# Sheet2.net
KiCad netlist of a schematic drawn in Altium Designer
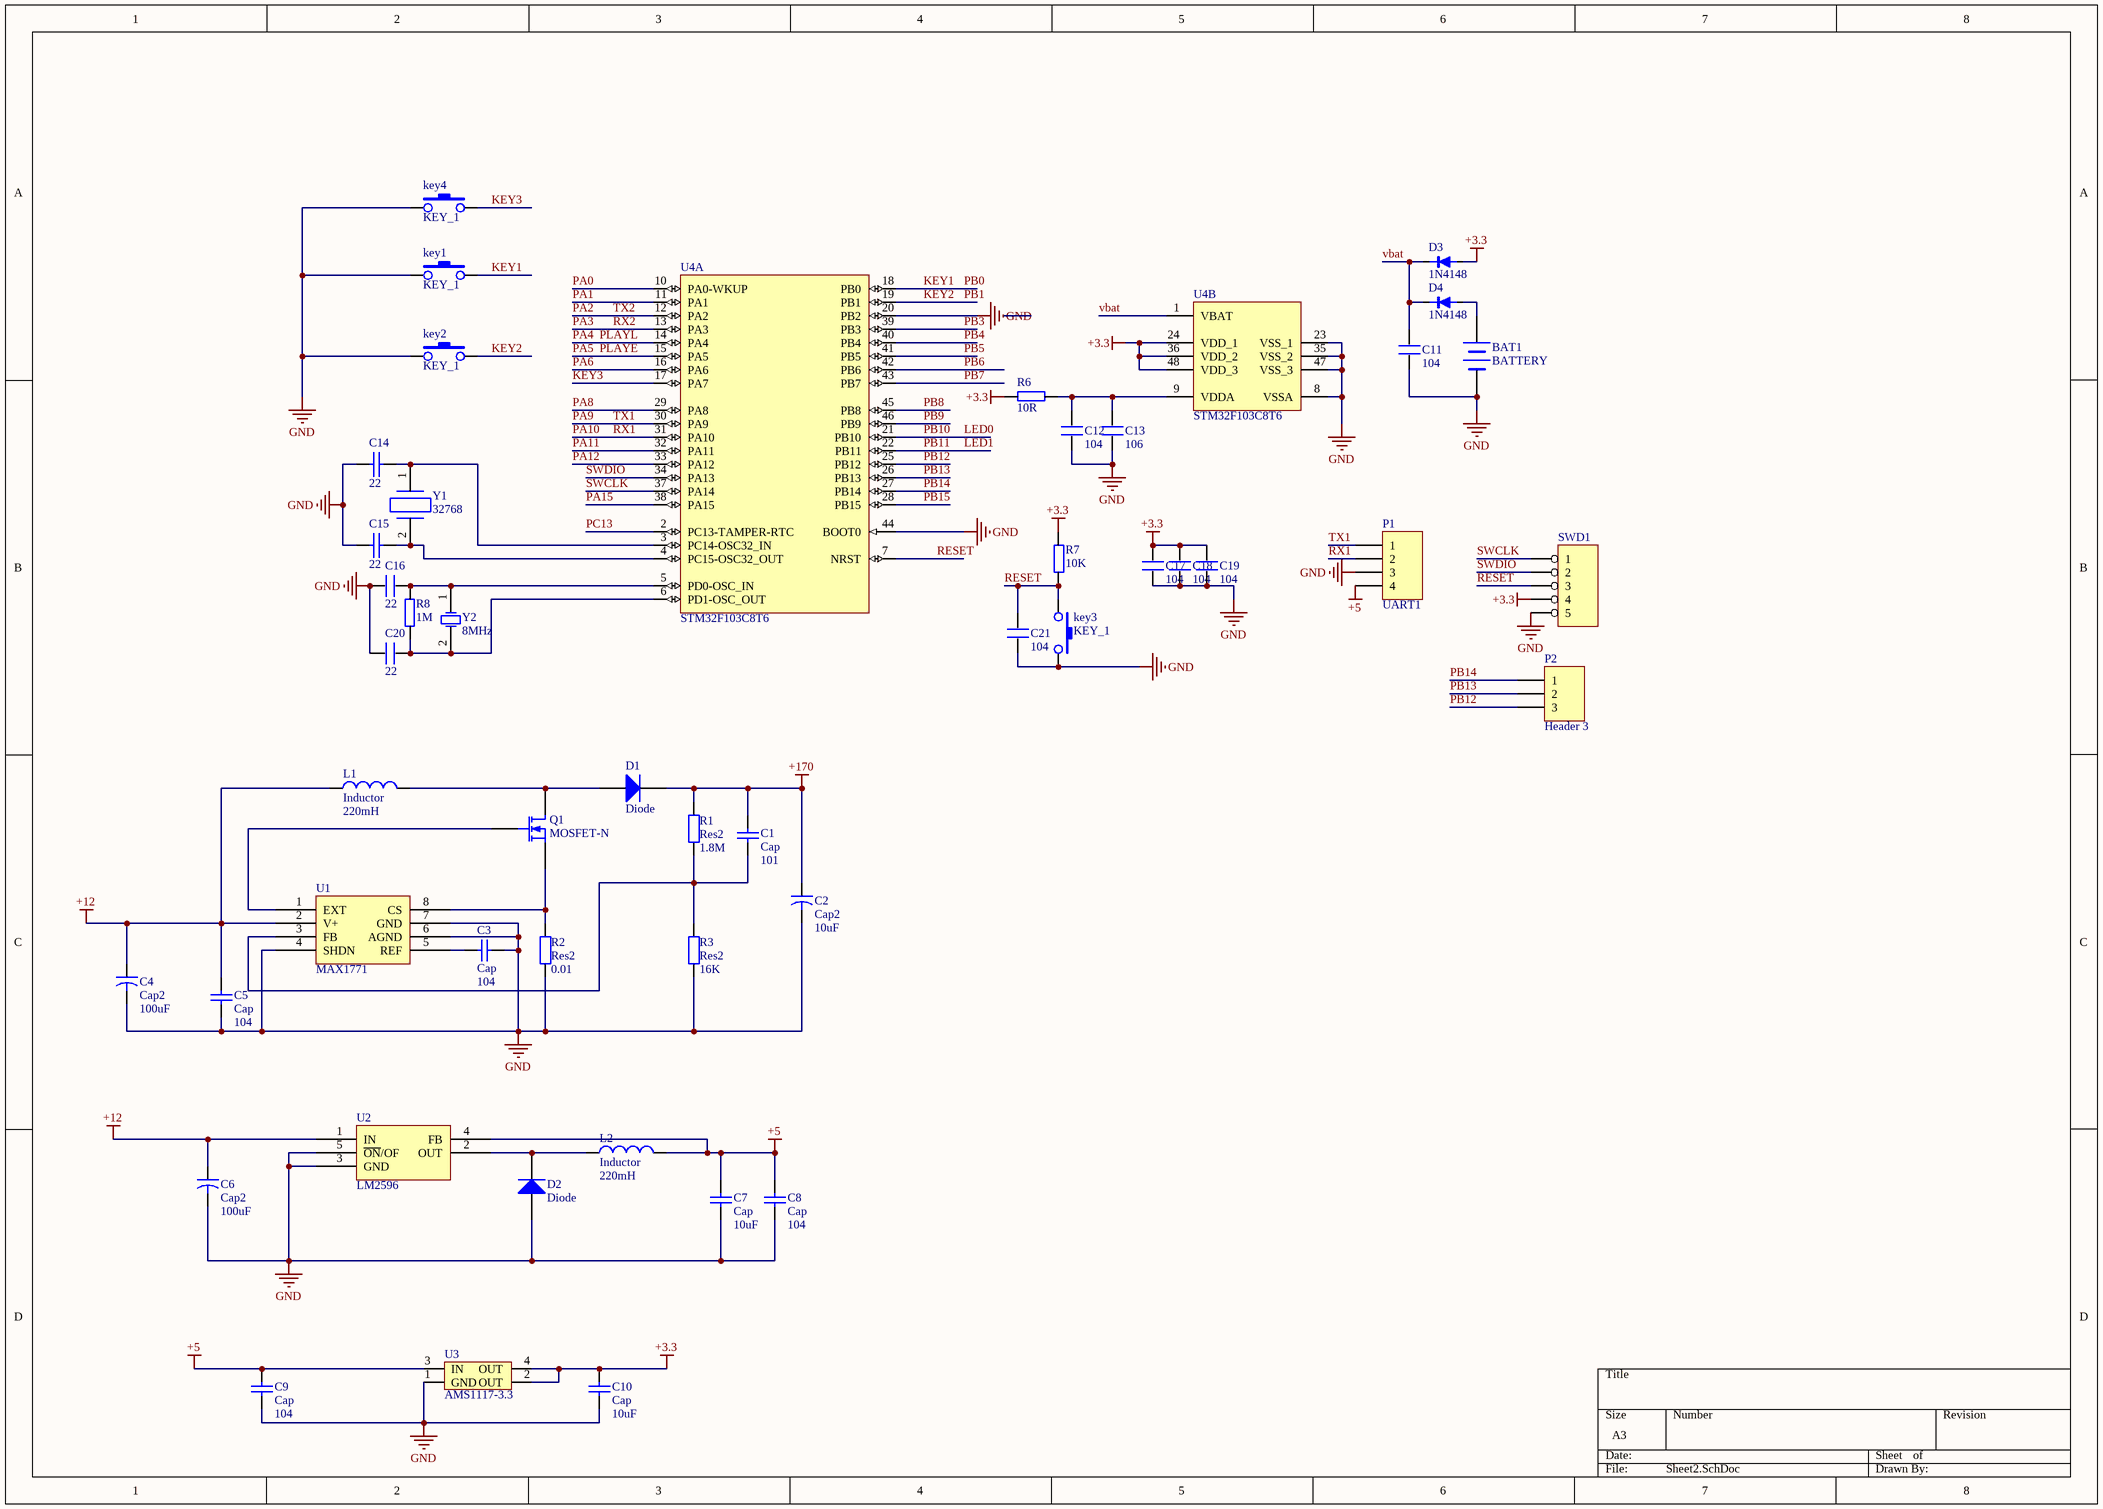
[diagram p0: Sheet2.SchDoc]

(export (version "E")
  (design (tool "Eeschema 10.0.6"))
  (components
    (comp (ref "BAT1") (value "BATTERY") (footprint "CR1220") (libsource (lib "常用元件库") (part "BATTERY")))
    (comp (ref "C1")
      (value "Cap")
      (footprint "1206C")
      (description "Capacitor")
      (fields (field (name "ALTIUM_VALUE") "101") (field (name "PUBLISHER") "Altium Limited"))
      (libsource (lib "Miscellaneous Devices") (part "Cap"))
    )
    (comp (ref "C2")
      (value "Cap2")
      (footprint "C10x16")
      (description "Capacitor")
      (fields (field (name "ALTIUM_VALUE") "10uF") (field (name "PUBLISHER") "Altium Limited"))
      (libsource (lib "Miscellaneous Devices") (part "Cap2"))
    )
    (comp (ref "C3")
      (value "Cap")
      (footprint "0805-0c")
      (description "Capacitor")
      (fields (field (name "ALTIUM_VALUE") "104") (field (name "PUBLISHER") "Altium Limited"))
      (libsource (lib "Miscellaneous Devices") (part "Cap"))
    )
    (comp (ref "C4")
      (value "Cap2")
      (footprint "C5X8")
      (description "Capacitor")
      (fields (field (name "ALTIUM_VALUE") "100uF") (field (name "PUBLISHER") "Altium Limited"))
      (libsource (lib "Miscellaneous Devices") (part "Cap2"))
    )
    (comp (ref "C5")
      (value "Cap")
      (footprint "0805-0c")
      (description "Capacitor")
      (fields (field (name "ALTIUM_VALUE") "104") (field (name "PUBLISHER") "Altium Limited"))
      (libsource (lib "Miscellaneous Devices") (part "Cap"))
    )
    (comp (ref "C6")
      (value "Cap2")
      (footprint "C5X8")
      (description "Capacitor")
      (fields (field (name "ALTIUM_VALUE") "100uF") (field (name "PUBLISHER") "Altium Limited"))
      (libsource (lib "Miscellaneous Devices") (part "Cap2"))
    )
    (comp (ref "C7")
      (value "Cap")
      (footprint "0805-0c")
      (description "Capacitor")
      (fields (field (name "ALTIUM_VALUE") "10uF") (field (name "PUBLISHER") "Altium Limited"))
      (libsource (lib "Miscellaneous Devices") (part "Cap"))
    )
    (comp (ref "C8")
      (value "Cap")
      (footprint "0805-0c")
      (description "Capacitor")
      (fields (field (name "ALTIUM_VALUE") "104") (field (name "PUBLISHER") "Altium Limited"))
      (libsource (lib "Miscellaneous Devices") (part "Cap"))
    )
    (comp (ref "C9")
      (value "Cap")
      (footprint "0805-0c")
      (description "Capacitor")
      (fields (field (name "ALTIUM_VALUE") "104") (field (name "PUBLISHER") "Altium Limited"))
      (libsource (lib "Miscellaneous Devices") (part "Cap"))
    )
    (comp (ref "C10")
      (value "Cap")
      (footprint "0805-0c")
      (description "Capacitor")
      (fields (field (name "ALTIUM_VALUE") "10uF") (field (name "PUBLISHER") "Altium Limited"))
      (libsource (lib "Miscellaneous Devices") (part "Cap"))
    )
    (comp (ref "C11") (value "104") (footprint "0805-0c") (libsource (lib "EXPLORER") (part "C")))
    (comp (ref "C12") (value "104") (footprint "0805-0c") (libsource (lib "EXPLORER") (part "C")))
    (comp (ref "C13") (value "106") (footprint "0805-0c") (libsource (lib "EXPLORER") (part "C")))
    (comp (ref "C14")
      (value "22")
      (footprint "0805-0c")
      (description "Capacitor")
      (libsource (lib "电容") (part "普通电容"))
    )
    (comp (ref "C15")
      (value "22")
      (footprint "0805-0c")
      (description "Capacitor")
      (libsource (lib "电容") (part "普通电容"))
    )
    (comp (ref "C16") (value "22") (footprint "0805-0c") (libsource (lib "EXPLORER") (part "C")))
    (comp (ref "C17") (value "104") (footprint "0805-0c") (libsource (lib "战舰STM32开发板底板封装库") (part "C")))
    (comp (ref "C18") (value "104") (footprint "0805-0c") (libsource (lib "战舰STM32开发板底板封装库") (part "C")))
    (comp (ref "C19") (value "104") (footprint "0805-0c") (libsource (lib "战舰STM32开发板底板封装库") (part "C")))
    (comp (ref "C20") (value "22") (footprint "0805-0c") (libsource (lib "EXPLORER") (part "C")))
    (comp (ref "C21") (value "104") (footprint "0805-0c") (libsource (lib "EXPLORER") (part "C")))
    (comp (ref "D1")
      (value "Diode")
      (footprint "DO-214")
      (description "Default Diode")
      (fields (field (name "PUBLISHER") "Altium Limited"))
      (libsource (lib "Miscellaneous Devices") (part "Diode"))
    )
    (comp (ref "D2")
      (value "Diode")
      (footprint "DO-214")
      (description "Default Diode")
      (fields (field (name "PUBLISHER") "Altium Limited"))
      (libsource (lib "Miscellaneous Devices") (part "Diode"))
    )
    (comp (ref "D3") (value "1N4148") (footprint "DO-214") (libsource (lib "元件库") (part "DIODE1")))
    (comp (ref "D4") (value "1N4148") (footprint "DO-214") (libsource (lib "元件库") (part "DIODE1")))
    (comp (ref "key1") (value "KEY_1") (footprint "KEY-DIP4W") (libsource (lib "元件库") (part "KEY_1")))
    (comp (ref "key2") (value "KEY_1") (footprint "KEY-DIP4W") (libsource (lib "元件库") (part "KEY_1")))
    (comp (ref "key3") (value "KEY_1") (footprint "KEY-SMD1") (libsource (lib "元件库") (part "KEY_1")))
    (comp (ref "key4") (value "KEY_1") (footprint "KEY-DIP4W") (libsource (lib "元件库") (part "KEY_1")))
    (comp (ref "L1")
      (value "Inductor")
      (footprint "L7X7")
      (fields (field (name "ALTIUM_VALUE") "220mH") (field (name "PUBLISHER") "Altium Limited"))
      (libsource (lib "Miscellaneous Devices") (part "Inductor"))
    )
    (comp (ref "L2")
      (value "Inductor")
      (footprint "L7X7")
      (fields (field (name "ALTIUM_VALUE") "220mH") (field (name "PUBLISHER") "Altium Limited"))
      (libsource (lib "Miscellaneous Devices") (part "Inductor"))
    )
    (comp (ref "P1")
      (value "UART1")
      (footprint "HDR1X4")
      (description "Header, 4-Pin")
      (fields (field (name "PUBLISHER") "Altium Limited"))
      (libsource (lib "EXPLORER") (part "Header 4"))
    )
    (comp (ref "P2")
      (value "Header 3")
      (footprint "HDR1X3")
      (description "Header, 3-Pin")
      (fields (field (name "PUBLISHER") "Altium Limited"))
      (libsource (lib "Miscellaneous Connectors") (part "Header 3"))
    )
    (comp (ref "Q1")
      (value "MOSFET-N")
      (footprint "TO-263-3")
      (description "N-Channel MOSFET")
      (fields (field (name "PUBLISHER") "Altium Limited"))
      (libsource (lib "Miscellaneous Devices") (part "MOSFET-N"))
    )
    (comp (ref "R1")
      (value "Res2")
      (footprint "0805-0r")
      (description "Resistor")
      (fields (field (name "ALTIUM_VALUE") "1.8M") (field (name "PUBLISHER") "Altium Limited"))
      (libsource (lib "Miscellaneous Devices") (part "Res2"))
    )
    (comp (ref "R2")
      (value "Res2")
      (footprint "0805-0r")
      (description "Resistor")
      (fields (field (name "ALTIUM_VALUE") "0.01") (field (name "PUBLISHER") "Altium Limited"))
      (libsource (lib "Miscellaneous Devices") (part "Res2"))
    )
    (comp (ref "R3")
      (value "Res2")
      (footprint "0805-0r")
      (description "Resistor")
      (fields (field (name "ALTIUM_VALUE") "16K") (field (name "PUBLISHER") "Altium Limited"))
      (libsource (lib "Miscellaneous Devices") (part "Res2"))
    )
    (comp (ref "R6") (value "10R") (footprint "0805-0r") (libsource (lib "EXPLORER") (part "R")))
    (comp (ref "R7") (value "10K") (footprint "0805-0r") (libsource (lib "EXPLORER") (part "R")))
    (comp (ref "R8") (value "1M") (footprint "0805-0r") (libsource (lib "EXPLORER") (part "R")))
    (comp (ref "SWD1") (value "HEADER 5") (footprint "HDR1X5") (libsource (lib "杂元件库") (part "HEADER 5")))
    (comp (ref "U1") (value "MAX1771") (footprint "sop8") (libsource (lib "Schlib1") (part "Component_1")))
    (comp (ref "U2")
      (value "LM2596")
      (footprint "TO263-5")
      (libsource (lib "LM2596-5V") (part "Component_1"))
    )
    (comp (ref "U3")
      (value "AMS1117-3.3")
      (footprint "SOT-223")
      (libsource (lib "战舰STM32开发板底板封装库") (part "AMS1117"))
    )
    (comp (ref "U4")
      (value "STM32F103C8T6")
      (footprint "STM-LQFP48_N")
      (libsource (lib "STMicroelectronics STM32 F1") (part "STM32F103C8T6"))
    )
    (comp (ref "Y1") (value "32768") (footprint "XTAL3X8") (libsource (lib "元件库") (part "XTAL")))
    (comp (ref "Y2")
      (value "8MHz")
      (footprint "XTAL-49S-DIP")
      (description "Crystal Oscillator")
      (fields (field (name "PUBLISHER") "Altium Limited"))
      (libsource (lib "EXPLORER") (part "XTAL"))
    )
  )
  (nets
    (net (code "1") (name "+3.3") (class "Default")
      (node (ref "C10") (pin "2") (pinfunction "2_2") (pintype "passive"))
      (node (ref "C17") (pin "2") (pintype "passive"))
      (node (ref "C18") (pin "2") (pintype "passive"))
      (node (ref "C19") (pin "2") (pintype "passive"))
      (node (ref "D3") (pin "1") (pinfunction "A_1") (pintype "passive"))
      (node (ref "R6") (pin "2") (pintype "passive"))
      (node (ref "R7") (pin "2") (pintype "passive"))
      (node (ref "SWD1") (pin "4") (pinfunction "4_4") (pintype "passive"))
      (node (ref "U3") (pin "2") (pinfunction "OUT_2") (pintype "passive"))
      (node (ref "U3") (pin "4") (pinfunction "OUT_4") (pintype "passive"))
      (node (ref "U4") (pin "24") (pinfunction "VDD_1_24") (pintype "power_in"))
      (node (ref "U4") (pin "36") (pinfunction "VDD_2_36") (pintype "power_in"))
      (node (ref "U4") (pin "48") (pinfunction "VDD_3_48") (pintype "power_in"))
    )
    (net (code "2") (name "+5") (class "Default")
      (node (ref "C7") (pin "2") (pinfunction "2_2") (pintype "passive"))
      (node (ref "C8") (pin "2") (pinfunction "2_2") (pintype "passive"))
      (node (ref "C9") (pin "2") (pinfunction "2_2") (pintype "passive"))
      (node (ref "L2") (pin "2") (pinfunction "2_2") (pintype "passive"))
      (node (ref "P1") (pin "4") (pinfunction "4_4") (pintype "passive"))
      (node (ref "U2") (pin "4") (pinfunction "FB_4") (pintype "passive"))
      (node (ref "U3") (pin "3") (pinfunction "IN_3") (pintype "passive"))
    )
    (net (code "3") (name "+12") (class "Default")
      (node (ref "C4") (pin "1") (pinfunction "1_1") (pintype "passive"))
      (node (ref "C5") (pin "2") (pinfunction "2_2") (pintype "passive"))
      (node (ref "C6") (pin "1") (pinfunction "1_1") (pintype "passive"))
      (node (ref "L1") (pin "1") (pinfunction "1_1") (pintype "passive"))
      (node (ref "U1") (pin "2") (pinfunction "V+_2") (pintype "passive"))
      (node (ref "U2") (pin "1") (pinfunction "IN_1") (pintype "passive"))
    )
    (net (code "4") (name "+170") (class "Default")
      (node (ref "C1") (pin "2") (pinfunction "2_2") (pintype "passive"))
      (node (ref "C2") (pin "1") (pinfunction "1_1") (pintype "passive"))
      (node (ref "D1") (pin "2") (pinfunction "K_2") (pintype "passive"))
      (node (ref "R1") (pin "2") (pinfunction "2_2") (pintype "passive"))
    )
    (net (code "5") (name "/KEY1") (class "Default")
      (node (ref "U4") (pin "18") (pinfunction "PB0_18") (pintype "bidirectional"))
      (node (ref "key1") (pin "2") (pinfunction "2_2") (pintype "passive"))
    )
    (net (code "6") (name "/KEY2") (class "Default")
      (node (ref "U4") (pin "19") (pinfunction "PB1_19") (pintype "bidirectional"))
      (node (ref "key2") (pin "2") (pinfunction "2_2") (pintype "passive"))
    )
    (net (code "7") (name "/KEY3") (class "Default")
      (node (ref "U4") (pin "17") (pinfunction "PA7_17") (pintype "bidirectional"))
      (node (ref "key4") (pin "2") (pinfunction "2_2") (pintype "passive"))
    )
    (net (code "8") (name "/LED0") (class "Default")
      (node (ref "U4") (pin "21") (pinfunction "PB10_21") (pintype "bidirectional"))
    )
    (net (code "9") (name "/LED1") (class "Default")
      (node (ref "U4") (pin "22") (pinfunction "PB11_22") (pintype "bidirectional"))
    )
    (net (code "10") (name "/PA0") (class "Default")
      (node (ref "U4") (pin "10") (pinfunction "PA0-WKUP_10") (pintype "bidirectional"))
    )
    (net (code "11") (name "/PA1") (class "Default")
      (node (ref "U4") (pin "11") (pinfunction "PA1_11") (pintype "bidirectional"))
    )
    (net (code "12") (name "/PA2") (class "Default")
      (node (ref "U4") (pin "12") (pinfunction "PA2_12") (pintype "bidirectional"))
    )
    (net (code "13") (name "/PA3") (class "Default")
      (node (ref "U4") (pin "13") (pinfunction "PA3_13") (pintype "bidirectional"))
    )
    (net (code "14") (name "/PA4") (class "Default")
      (node (ref "U4") (pin "14") (pinfunction "PA4_14") (pintype "bidirectional"))
    )
    (net (code "15") (name "/PA5") (class "Default")
      (node (ref "U4") (pin "15") (pinfunction "PA5_15") (pintype "bidirectional"))
    )
    (net (code "16") (name "/PA6") (class "Default")
      (node (ref "U4") (pin "16") (pinfunction "PA6_16") (pintype "bidirectional"))
    )
    (net (code "17") (name "/PA8") (class "Default")
      (node (ref "U4") (pin "29") (pinfunction "PA8_29") (pintype "bidirectional"))
    )
    (net (code "18") (name "/PA9") (class "Default")
      (node (ref "P1") (pin "1") (pinfunction "1_1") (pintype "passive"))
      (node (ref "U4") (pin "30") (pinfunction "PA9_30") (pintype "bidirectional"))
    )
    (net (code "19") (name "/PA10") (class "Default")
      (node (ref "P1") (pin "2") (pinfunction "2_2") (pintype "passive"))
      (node (ref "U4") (pin "31") (pinfunction "PA10_31") (pintype "bidirectional"))
    )
    (net (code "20") (name "/PA11") (class "Default")
      (node (ref "U4") (pin "32") (pinfunction "PA11_32") (pintype "bidirectional"))
    )
    (net (code "21") (name "/PA12") (class "Default")
      (node (ref "U4") (pin "33") (pinfunction "PA12_33") (pintype "bidirectional"))
    )
    (net (code "22") (name "/PA15") (class "Default")
      (node (ref "U4") (pin "38") (pinfunction "PA15_38") (pintype "bidirectional"))
    )
    (net (code "23") (name "/PB3") (class "Default")
      (node (ref "U4") (pin "39") (pinfunction "PB3_39") (pintype "bidirectional"))
    )
    (net (code "24") (name "/PB4") (class "Default")
      (node (ref "U4") (pin "40") (pinfunction "PB4_40") (pintype "bidirectional"))
    )
    (net (code "25") (name "/PB5") (class "Default")
      (node (ref "U4") (pin "41") (pinfunction "PB5_41") (pintype "bidirectional"))
    )
    (net (code "26") (name "/PB6") (class "Default")
      (node (ref "U4") (pin "42") (pinfunction "PB6_42") (pintype "bidirectional"))
    )
    (net (code "27") (name "/PB7") (class "Default")
      (node (ref "U4") (pin "43") (pinfunction "PB7_43") (pintype "bidirectional"))
    )
    (net (code "28") (name "/PB8") (class "Default")
      (node (ref "U4") (pin "45") (pinfunction "PB8_45") (pintype "bidirectional"))
    )
    (net (code "29") (name "/PB9") (class "Default")
      (node (ref "U4") (pin "46") (pinfunction "PB9_46") (pintype "bidirectional"))
    )
    (net (code "30") (name "/PB12") (class "Default")
      (node (ref "P2") (pin "3") (pinfunction "3_3") (pintype "passive"))
      (node (ref "U4") (pin "25") (pinfunction "PB12_25") (pintype "bidirectional"))
    )
    (net (code "31") (name "/PB13") (class "Default")
      (node (ref "P2") (pin "2") (pinfunction "2_2") (pintype "passive"))
      (node (ref "U4") (pin "26") (pinfunction "PB13_26") (pintype "bidirectional"))
    )
    (net (code "32") (name "/PB14") (class "Default")
      (node (ref "P2") (pin "1") (pinfunction "1_1") (pintype "passive"))
      (node (ref "U4") (pin "27") (pinfunction "PB14_27") (pintype "bidirectional"))
    )
    (net (code "33") (name "/PB15") (class "Default")
      (node (ref "U4") (pin "28") (pinfunction "PB15_28") (pintype "bidirectional"))
    )
    (net (code "34") (name "/PC13") (class "Default")
      (node (ref "U4") (pin "2") (pinfunction "PC13-TAMPER-RTC_2") (pintype "bidirectional"))
    )
    (net (code "35") (name "/RESET") (class "Default")
      (node (ref "C21") (pin "1") (pintype "passive"))
      (node (ref "R7") (pin "1") (pintype "passive"))
      (node (ref "SWD1") (pin "3") (pinfunction "3_3") (pintype "passive"))
      (node (ref "U4") (pin "7") (pinfunction "NRST_7") (pintype "bidirectional"))
      (node (ref "key3") (pin "1") (pinfunction "1_1") (pintype "passive"))
    )
    (net (code "36") (name "/SWCLK") (class "Default")
      (node (ref "SWD1") (pin "1") (pinfunction "1_1") (pintype "passive"))
      (node (ref "U4") (pin "37") (pinfunction "PA14_37") (pintype "bidirectional"))
    )
    (net (code "37") (name "/SWDIO") (class "Default")
      (node (ref "SWD1") (pin "2") (pinfunction "2_2") (pintype "passive"))
      (node (ref "U4") (pin "34") (pinfunction "PA13_34") (pintype "bidirectional"))
    )
    (net (code "38") (name "/vbat") (class "Default")
      (node (ref "C11") (pin "2") (pintype "passive"))
      (node (ref "D3") (pin "2") (pinfunction "K_2") (pintype "passive"))
      (node (ref "D4") (pin "2") (pinfunction "K_2") (pintype "passive"))
      (node (ref "U4") (pin "1") (pinfunction "VBAT_1") (pintype "power_in"))
    )
    (net (code "39") (name "GND") (class "Default")
      (node (ref "BAT1") (pin "2") (pinfunction "-_2") (pintype "passive"))
      (node (ref "C10") (pin "1") (pinfunction "1_1") (pintype "passive"))
      (node (ref "C11") (pin "1") (pintype "passive"))
      (node (ref "C12") (pin "1") (pintype "passive"))
      (node (ref "C13") (pin "1") (pintype "passive"))
      (node (ref "C14") (pin "1") (pinfunction "1_1") (pintype "passive"))
      (node (ref "C15") (pin "1") (pinfunction "1_1") (pintype "passive"))
      (node (ref "C16") (pin "1") (pintype "passive"))
      (node (ref "C17") (pin "1") (pintype "passive"))
      (node (ref "C18") (pin "1") (pintype "passive"))
      (node (ref "C19") (pin "1") (pintype "passive"))
      (node (ref "C2") (pin "2") (pinfunction "2_2") (pintype "passive"))
      (node (ref "C20") (pin "1") (pintype "passive"))
      (node (ref "C21") (pin "2") (pintype "passive"))
      (node (ref "C3") (pin "2") (pinfunction "2_2") (pintype "passive"))
      (node (ref "C4") (pin "2") (pinfunction "2_2") (pintype "passive"))
      (node (ref "C5") (pin "1") (pinfunction "1_1") (pintype "passive"))
      (node (ref "C6") (pin "2") (pinfunction "2_2") (pintype "passive"))
      (node (ref "C7") (pin "1") (pinfunction "1_1") (pintype "passive"))
      (node (ref "C8") (pin "1") (pinfunction "1_1") (pintype "passive"))
      (node (ref "C9") (pin "1") (pinfunction "1_1") (pintype "passive"))
      (node (ref "D2") (pin "1") (pinfunction "A_1") (pintype "passive"))
      (node (ref "P1") (pin "3") (pinfunction "3_3") (pintype "passive"))
      (node (ref "R2") (pin "1") (pinfunction "1_1") (pintype "passive"))
      (node (ref "R3") (pin "1") (pinfunction "1_1") (pintype "passive"))
      (node (ref "SWD1") (pin "5") (pinfunction "5_5") (pintype "passive"))
      (node (ref "U1") (pin "4") (pinfunction "SHDN_4") (pintype "passive"))
      (node (ref "U1") (pin "6") (pinfunction "AGND_6") (pintype "passive"))
      (node (ref "U1") (pin "7") (pinfunction "GND_7") (pintype "passive"))
      (node (ref "U2") (pin "3") (pinfunction "GND_3") (pintype "passive"))
      (node (ref "U2") (pin "5") (pinfunction "~{ON}/OF_5") (pintype "passive"))
      (node (ref "U3") (pin "1") (pinfunction "GND_1") (pintype "passive"))
      (node (ref "U4") (pin "20") (pinfunction "PB2_20") (pintype "bidirectional"))
      (node (ref "U4") (pin "23") (pinfunction "VSS_1_23") (pintype "power_in"))
      (node (ref "U4") (pin "35") (pinfunction "VSS_2_35") (pintype "power_in"))
      (node (ref "U4") (pin "44") (pinfunction "BOOT0_44") (pintype "input"))
      (node (ref "U4") (pin "47") (pinfunction "VSS_3_47") (pintype "power_in"))
      (node (ref "U4") (pin "8") (pinfunction "VSSA_8") (pintype "power_in"))
      (node (ref "key1") (pin "1") (pinfunction "1_1") (pintype "passive"))
      (node (ref "key2") (pin "1") (pinfunction "1_1") (pintype "passive"))
      (node (ref "key3") (pin "2") (pinfunction "2_2") (pintype "passive"))
      (node (ref "key4") (pin "1") (pinfunction "1_1") (pintype "passive"))
    )
    (net (code "40") (name "Net-(BAT1-+)") (class "Default")
      (node (ref "BAT1") (pin "1") (pinfunction "+_1") (pintype "passive"))
      (node (ref "D4") (pin "1") (pinfunction "A_1") (pintype "passive"))
    )
    (net (code "41") (name "Net-(D1-A)") (class "Default")
      (node (ref "D1") (pin "1") (pinfunction "A_1") (pintype "passive"))
      (node (ref "L1") (pin "2") (pinfunction "2_2") (pintype "passive"))
      (node (ref "Q1") (pin "1") (pinfunction "D_1") (pintype "passive"))
    )
    (net (code "42") (name "Net-(D2-K)") (class "Default")
      (node (ref "D2") (pin "2") (pinfunction "K_2") (pintype "passive"))
      (node (ref "L2") (pin "1") (pinfunction "1_1") (pintype "passive"))
      (node (ref "U2") (pin "2") (pinfunction "OUT_2") (pintype "passive"))
    )
    (net (code "43") (name "Net-(Q1-G)") (class "Default")
      (node (ref "Q1") (pin "2") (pinfunction "G_2") (pintype "passive"))
      (node (ref "U1") (pin "1") (pinfunction "EXT_1") (pintype "passive"))
    )
    (net (code "44") (name "Net-(Q1-S)") (class "Default")
      (node (ref "Q1") (pin "3") (pinfunction "S_3") (pintype "passive"))
      (node (ref "R2") (pin "2") (pinfunction "2_2") (pintype "passive"))
      (node (ref "U1") (pin "8") (pinfunction "CS_8") (pintype "passive"))
    )
    (net (code "45") (name "Net-(U1-FB)") (class "Default")
      (node (ref "C1") (pin "1") (pinfunction "1_1") (pintype "passive"))
      (node (ref "R1") (pin "1") (pinfunction "1_1") (pintype "passive"))
      (node (ref "R3") (pin "2") (pinfunction "2_2") (pintype "passive"))
      (node (ref "U1") (pin "3") (pinfunction "FB_3") (pintype "passive"))
    )
    (net (code "46") (name "Net-(U1-REF)") (class "Default")
      (node (ref "C3") (pin "1") (pinfunction "1_1") (pintype "passive"))
      (node (ref "U1") (pin "5") (pinfunction "REF_5") (pintype "passive"))
    )
    (net (code "47") (name "Net-(U4A-PC14-OSC32_IN)") (class "Default")
      (node (ref "C14") (pin "2") (pinfunction "2_2") (pintype "passive"))
      (node (ref "U4") (pin "3") (pinfunction "PC14-OSC32_IN_3") (pintype "bidirectional"))
      (node (ref "Y1") (pin "1") (pinfunction "1_1") (pintype "passive"))
    )
    (net (code "48") (name "Net-(U4A-PC15-OSC32_OUT)") (class "Default")
      (node (ref "C15") (pin "2") (pinfunction "2_2") (pintype "passive"))
      (node (ref "U4") (pin "4") (pinfunction "PC15-OSC32_OUT_4") (pintype "bidirectional"))
      (node (ref "Y1") (pin "2") (pinfunction "2_2") (pintype "passive"))
    )
    (net (code "49") (name "Net-(U4A-PD0-OSC_IN)") (class "Default")
      (node (ref "C16") (pin "2") (pintype "passive"))
      (node (ref "R8") (pin "1") (pintype "passive"))
      (node (ref "U4") (pin "5") (pinfunction "PD0-OSC_IN_5") (pintype "bidirectional"))
      (node (ref "Y2") (pin "1") (pinfunction "OSC1_1") (pintype "passive"))
    )
    (net (code "50") (name "Net-(U4A-PD1-OSC_OUT)") (class "Default")
      (node (ref "C20") (pin "2") (pintype "passive"))
      (node (ref "R8") (pin "2") (pintype "passive"))
      (node (ref "U4") (pin "6") (pinfunction "PD1-OSC_OUT_6") (pintype "bidirectional"))
      (node (ref "Y2") (pin "2") (pinfunction "OSC2_2") (pintype "passive"))
    )
    (net (code "51") (name "Net-(U4B-VDDA)") (class "Default")
      (node (ref "C12") (pin "2") (pintype "passive"))
      (node (ref "C13") (pin "2") (pintype "passive"))
      (node (ref "R6") (pin "1") (pintype "passive"))
      (node (ref "U4") (pin "9") (pinfunction "VDDA_9") (pintype "power_in"))
    )
  )
)
